# ems.net
KiCad netlist of a schematic drawn in Altium Designer
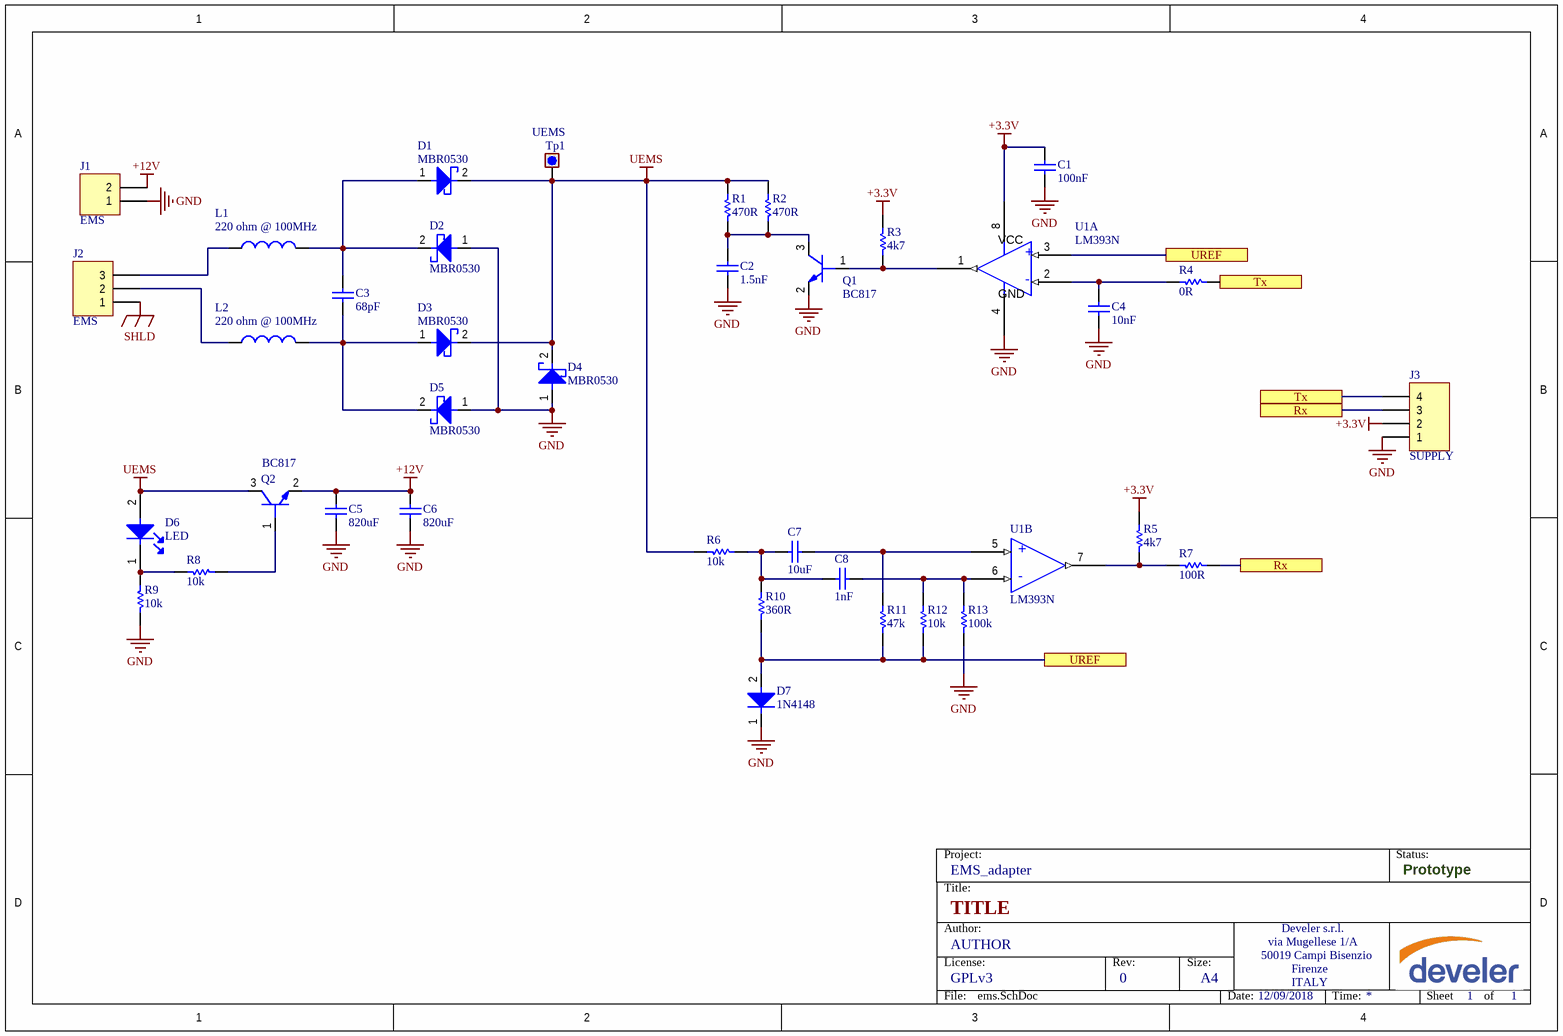
[diagram p0: ems.SchDoc]

(export (version "E")
  (design (tool "Eeschema 10.0.6"))
  (components
    (comp (ref "C1")
      (value "100nF")
      (footprint "0603_[1608]")
      (description "Ceramic X7R 50V")
      (fields (field (name "PUBLISHER") "Altium Limited"))
      (libsource (lib "DEVELER_Library") (part "Cap"))
    )
    (comp (ref "C2")
      (value "1.5nF")
      (footprint "0603_[1608]")
      (description "Ceramic X7R 50V")
      (fields (field (name "PUBLISHER") "Altium Limited"))
      (libsource (lib "DEVELER_Library") (part "Cap"))
    )
    (comp (ref "C3")
      (value "68pF")
      (footprint "0603_[1608]")
      (description "Ceramic X7R 50V")
      (fields (field (name "PUBLISHER") "Altium Limited"))
      (libsource (lib "DEVELER_Library") (part "Cap"))
    )
    (comp (ref "C4")
      (value "10nF")
      (footprint "0603_[1608]")
      (description "Ceramic X7R 50V")
      (fields (field (name "PUBLISHER") "Altium Limited"))
      (libsource (lib "DEVELER_Library") (part "Cap"))
    )
    (comp (ref "C5")
      (value "820uF")
      (footprint "CAP_CYL_3.5mm_D8mm")
      (description "Ceramic X7R 50V")
      (fields (field (name "PUBLISHER") "Altium Limited"))
      (libsource (lib "DEVELER_Library") (part "Cap"))
    )
    (comp (ref "C6")
      (value "820uF")
      (footprint "CAP_CYL_3.5mm_D8mm")
      (description "Ceramic X7R 50V")
      (fields (field (name "PUBLISHER") "Altium Limited"))
      (libsource (lib "DEVELER_Library") (part "Cap"))
    )
    (comp (ref "C7")
      (value "10uF")
      (footprint "0603_[1608]")
      (description "Ceramic X7R 50V")
      (fields (field (name "PUBLISHER") "Altium Limited"))
      (libsource (lib "DEVELER_Library") (part "Cap"))
    )
    (comp (ref "C8")
      (value "1nF")
      (footprint "0603_[1608]")
      (description "Ceramic X7R 50V")
      (fields (field (name "PUBLISHER") "Altium Limited"))
      (libsource (lib "DEVELER_Library") (part "Cap"))
    )
    (comp (ref "D1")
      (value "MBR0530")
      (footprint "SOD-123_K2-A1")
      (description "Schottky Diodes")
      (libsource (lib "develer_library") (part "Diode_SCHOTTKY"))
    )
    (comp (ref "D2")
      (value "MBR0530")
      (footprint "SOD-123_K2-A1")
      (description "Schottky Diodes")
      (libsource (lib "develer_library") (part "Diode_SCHOTTKY"))
    )
    (comp (ref "D3")
      (value "MBR0530")
      (footprint "SOD-123_K2-A1")
      (description "Schottky Diodes")
      (libsource (lib "develer_library") (part "Diode_SCHOTTKY"))
    )
    (comp (ref "D4")
      (value "MBR0530")
      (footprint "SOD-123_K2-A1")
      (description "Schottky Diodes")
      (libsource (lib "develer_library") (part "Diode_SCHOTTKY"))
    )
    (comp (ref "D5")
      (value "MBR0530")
      (footprint "SOD-123_K2-A1")
      (description "Schottky Diodes")
      (libsource (lib "develer_library") (part "Diode_SCHOTTKY"))
    )
    (comp (ref "D6")
      (value "LED")
      (footprint "1206_[3216]_K1-A2_LED")
      (description "Multicolor LED")
      (libsource (lib "develer_library") (part "LED"))
    )
    (comp (ref "D7")
      (value "1N4148")
      (footprint "SOD-80C")
      (libsource (lib "develer_library") (part "Diode"))
    )
    (comp (ref "J1")
      (value "EMS")
      (footprint "CON_2P_WAGO_3.5mm")
      (description "Header, 2-Pin")
      (fields (field (name "PUBLISHER") "Altium Limited"))
      (libsource (lib "Miscellaneous Connectors") (part "Header 2"))
    )
    (comp (ref "J2")
      (value "EMS")
      (footprint "CON_3P_WAGO_3.5mm")
      (description "Header, 3-Pin")
      (fields (field (name "PUBLISHER") "Altium Limited"))
      (libsource (lib "Miscellaneous Connectors") (part "Header 3"))
    )
    (comp (ref "J3")
      (value "SUPPLY")
      (footprint "CON_4P_WAGO_3.5mm")
      (description "Header, 4-Pin")
      (fields (field (name "PUBLISHER") "Altium Limited"))
      (libsource (lib "Miscellaneous Connectors") (part "Header 4"))
    )
    (comp (ref "L1")
      (value "220 ohm @ 100MHz")
      (footprint "0805_[2012]")
      (description "WE 742792022")
      (libsource (lib "DEVELER_Library") (part "Ferrite Bead"))
    )
    (comp (ref "L2")
      (value "220 ohm @ 100MHz")
      (footprint "0805_[2012]")
      (description "WE 742792022")
      (libsource (lib "DEVELER_Library") (part "Ferrite Bead"))
    )
    (comp (ref "Q1")
      (value "BC817")
      (footprint "SOT-23")
      (description "BJT NPN")
      (libsource (lib "develer_library") (part "BC817"))
    )
    (comp (ref "Q2")
      (value "BC817")
      (footprint "SOT-23")
      (description "BJT NPN")
      (libsource (lib "develer_library") (part "BC817"))
    )
    (comp (ref "R1")
      (value "470R")
      (footprint "0603_[1608]")
      (description "Resistor")
      (fields (field (name "PUBLISHER") "Altium Limited"))
      (libsource (lib "DEVELER_Library") (part "Res1"))
    )
    (comp (ref "R2")
      (value "470R")
      (footprint "0603_[1608]")
      (description "Resistor")
      (fields (field (name "PUBLISHER") "Altium Limited"))
      (libsource (lib "DEVELER_Library") (part "Res1"))
    )
    (comp (ref "R3")
      (value "4k7")
      (footprint "0603_[1608]")
      (description "Resistor")
      (fields (field (name "PUBLISHER") "Altium Limited"))
      (libsource (lib "DEVELER_Library") (part "Res1"))
    )
    (comp (ref "R4")
      (value "0R")
      (footprint "0603_[1608]")
      (description "Resistor")
      (fields (field (name "PUBLISHER") "Altium Limited"))
      (libsource (lib "DEVELER_Library") (part "Res1"))
    )
    (comp (ref "R5")
      (value "4k7")
      (footprint "0603_[1608]")
      (description "Resistor")
      (fields (field (name "PUBLISHER") "Altium Limited"))
      (libsource (lib "DEVELER_Library") (part "Res1"))
    )
    (comp (ref "R6")
      (value "10k")
      (footprint "0603_[1608]")
      (description "Resistor")
      (fields (field (name "PUBLISHER") "Altium Limited"))
      (libsource (lib "DEVELER_Library") (part "Res1"))
    )
    (comp (ref "R7")
      (value "100R")
      (footprint "0603_[1608]")
      (description "Resistor")
      (fields (field (name "PUBLISHER") "Altium Limited"))
      (libsource (lib "DEVELER_Library") (part "Res1"))
    )
    (comp (ref "R8")
      (value "10k")
      (footprint "0603_[1608]")
      (description "Resistor")
      (fields (field (name "PUBLISHER") "Altium Limited"))
      (libsource (lib "DEVELER_Library") (part "Res1"))
    )
    (comp (ref "R9")
      (value "10k")
      (footprint "0603_[1608]")
      (description "Resistor")
      (fields (field (name "PUBLISHER") "Altium Limited"))
      (libsource (lib "DEVELER_Library") (part "Res1"))
    )
    (comp (ref "R10")
      (value "360R")
      (footprint "0603_[1608]")
      (description "Resistor")
      (fields (field (name "PUBLISHER") "Altium Limited"))
      (libsource (lib "DEVELER_Library") (part "Res1"))
    )
    (comp (ref "R11")
      (value "47k")
      (footprint "0603_[1608]")
      (description "Resistor")
      (fields (field (name "PUBLISHER") "Altium Limited"))
      (libsource (lib "DEVELER_Library") (part "Res1"))
    )
    (comp (ref "R12")
      (value "10k")
      (footprint "0603_[1608]")
      (description "Resistor")
      (fields (field (name "PUBLISHER") "Altium Limited"))
      (libsource (lib "DEVELER_Library") (part "Res1"))
    )
    (comp (ref "R13")
      (value "100k")
      (footprint "0603_[1608]")
      (description "Resistor")
      (fields (field (name "PUBLISHER") "Altium Limited"))
      (libsource (lib "DEVELER_Library") (part "Res1"))
    )
    (comp (ref "Tp1")
      (value "UEMS")
      (footprint "TEST_POINT_THD_D1.8MM")
      (description "Test point")
      (libsource (lib "DEVELER_Library") (part "Test_point"))
    )
    (comp (ref "U1")
      (value "LM393N")
      (footprint "SOIC8")
      (description "Op Amp.")
      (libsource (lib "develer_library") (part "LM358"))
    )
  )
  (nets
    (net (code "1") (name "+3.3V") (class "Default")
      (node (ref "C1") (pin "2") (pinfunction "2_2") (pintype "passive"))
      (node (ref "J3") (pin "2") (pinfunction "2_2") (pintype "passive"))
      (node (ref "R3") (pin "1") (pinfunction "1_1") (pintype "passive"))
      (node (ref "R5") (pin "1") (pinfunction "1_1") (pintype "passive"))
      (node (ref "U1") (pin "8") (pinfunction "VCC_8") (pintype "power_in"))
    )
    (net (code "2") (name "+12V") (class "Default")
      (node (ref "C5") (pin "2") (pinfunction "2_2") (pintype "passive"))
      (node (ref "C6") (pin "2") (pinfunction "2_2") (pintype "passive"))
      (node (ref "J1") (pin "2") (pinfunction "2_2") (pintype "passive"))
      (node (ref "Q2") (pin "2") (pinfunction "E_2") (pintype "passive"))
    )
    (net (code "3") (name "/Rx") (class "Default")
      (node (ref "J3") (pin "3") (pinfunction "3_3") (pintype "passive"))
      (node (ref "R7") (pin "2") (pinfunction "2_2") (pintype "passive"))
    )
    (net (code "4") (name "/Tx") (class "Default")
      (node (ref "J3") (pin "4") (pinfunction "4_4") (pintype "passive"))
      (node (ref "R4") (pin "2") (pinfunction "2_2") (pintype "passive"))
    )
    (net (code "5") (name "/UREF") (class "Default")
      (node (ref "D7") (pin "2") (pinfunction "A_2") (pintype "passive"))
      (node (ref "R10") (pin "1") (pinfunction "1_1") (pintype "passive"))
      (node (ref "R11") (pin "1") (pinfunction "1_1") (pintype "passive"))
      (node (ref "R12") (pin "1") (pinfunction "1_1") (pintype "passive"))
      (node (ref "U1") (pin "3") (pinfunction "IN+_3") (pintype "input"))
    )
    (net (code "6") (name "GND") (class "Default")
      (node (ref "C1") (pin "1") (pinfunction "1_1") (pintype "passive"))
      (node (ref "C2") (pin "1") (pinfunction "1_1") (pintype "passive"))
      (node (ref "C4") (pin "1") (pinfunction "1_1") (pintype "passive"))
      (node (ref "C5") (pin "1") (pinfunction "1_1") (pintype "passive"))
      (node (ref "C6") (pin "1") (pinfunction "1_1") (pintype "passive"))
      (node (ref "D2") (pin "1") (pinfunction "A_1") (pintype "passive"))
      (node (ref "D4") (pin "1") (pinfunction "A_1") (pintype "passive"))
      (node (ref "D5") (pin "1") (pinfunction "A_1") (pintype "passive"))
      (node (ref "D7") (pin "1") (pinfunction "K_1") (pintype "passive"))
      (node (ref "J1") (pin "1") (pinfunction "1_1") (pintype "passive"))
      (node (ref "J3") (pin "1") (pinfunction "1_1") (pintype "passive"))
      (node (ref "Q1") (pin "2") (pinfunction "E_2") (pintype "passive"))
      (node (ref "R13") (pin "1") (pinfunction "1_1") (pintype "passive"))
      (node (ref "R9") (pin "1") (pinfunction "1_1") (pintype "passive"))
      (node (ref "U1") (pin "4") (pinfunction "GND_4") (pintype "power_in"))
    )
    (net (code "7") (name "Net-(C7-Pad2)") (class "Default")
      (node (ref "C7") (pin "2") (pinfunction "2_2") (pintype "passive"))
      (node (ref "C8") (pin "2") (pinfunction "2_2") (pintype "passive"))
      (node (ref "R10") (pin "2") (pinfunction "2_2") (pintype "passive"))
      (node (ref "R6") (pin "2") (pinfunction "2_2") (pintype "passive"))
    )
    (net (code "8") (name "Net-(D1-A)") (class "Default")
      (node (ref "C3") (pin "2") (pinfunction "2_2") (pintype "passive"))
      (node (ref "D1") (pin "1") (pinfunction "A_1") (pintype "passive"))
      (node (ref "D2") (pin "2") (pinfunction "K_2") (pintype "passive"))
      (node (ref "L1") (pin "1") (pinfunction "1_1") (pintype "passive"))
    )
    (net (code "9") (name "Net-(D3-A)") (class "Default")
      (node (ref "C3") (pin "1") (pinfunction "1_1") (pintype "passive"))
      (node (ref "D3") (pin "1") (pinfunction "A_1") (pintype "passive"))
      (node (ref "D5") (pin "2") (pinfunction "K_2") (pintype "passive"))
      (node (ref "L2") (pin "1") (pinfunction "1_1") (pintype "passive"))
    )
    (net (code "10") (name "Net-(D6-K)") (class "Default")
      (node (ref "D6") (pin "1") (pinfunction "K_1") (pintype "passive"))
      (node (ref "R8") (pin "2") (pinfunction "2_2") (pintype "passive"))
      (node (ref "R9") (pin "2") (pinfunction "2_2") (pintype "passive"))
    )
    (net (code "11") (name "Net-(J2-Pad2)") (class "Default")
      (node (ref "J2") (pin "2") (pinfunction "2_2") (pintype "passive"))
      (node (ref "L2") (pin "2") (pinfunction "2_2") (pintype "passive"))
    )
    (net (code "12") (name "Net-(J2-Pad3)") (class "Default")
      (node (ref "J2") (pin "3") (pinfunction "3_3") (pintype "passive"))
      (node (ref "L1") (pin "2") (pinfunction "2_2") (pintype "passive"))
    )
    (net (code "13") (name "Net-(Q1-B)") (class "Default")
      (node (ref "Q1") (pin "1") (pinfunction "B_1") (pintype "passive"))
      (node (ref "R3") (pin "2") (pinfunction "2_2") (pintype "passive"))
      (node (ref "U1") (pin "1") (pinfunction "OUT_1") (pintype "output"))
    )
    (net (code "14") (name "Net-(Q1-C)") (class "Default")
      (node (ref "C2") (pin "2") (pinfunction "2_2") (pintype "passive"))
      (node (ref "Q1") (pin "3") (pinfunction "C_3") (pintype "passive"))
      (node (ref "R1") (pin "2") (pinfunction "2_2") (pintype "passive"))
      (node (ref "R2") (pin "2") (pinfunction "2_2") (pintype "passive"))
    )
    (net (code "15") (name "Net-(Q2-B)") (class "Default")
      (node (ref "Q2") (pin "1") (pinfunction "B_1") (pintype "passive"))
      (node (ref "R8") (pin "1") (pinfunction "1_1") (pintype "passive"))
    )
    (net (code "16") (name "Net-(U1A-IN-)") (class "Default")
      (node (ref "C4") (pin "2") (pinfunction "2_2") (pintype "passive"))
      (node (ref "R4") (pin "1") (pinfunction "1_1") (pintype "passive"))
      (node (ref "U1") (pin "2") (pinfunction "IN-_2") (pintype "input"))
    )
    (net (code "17") (name "Net-(U1B-IN+)") (class "Default")
      (node (ref "C7") (pin "1") (pinfunction "1_1") (pintype "passive"))
      (node (ref "R11") (pin "2") (pinfunction "2_2") (pintype "passive"))
      (node (ref "U1") (pin "5") (pinfunction "IN+_5") (pintype "input"))
    )
    (net (code "18") (name "Net-(U1B-IN-)") (class "Default")
      (node (ref "C8") (pin "1") (pinfunction "1_1") (pintype "passive"))
      (node (ref "R12") (pin "2") (pinfunction "2_2") (pintype "passive"))
      (node (ref "R13") (pin "2") (pinfunction "2_2") (pintype "passive"))
      (node (ref "U1") (pin "6") (pinfunction "IN-_6") (pintype "input"))
    )
    (net (code "19") (name "Net-(U1B-OUT)") (class "Default")
      (node (ref "R5") (pin "2") (pinfunction "2_2") (pintype "passive"))
      (node (ref "R7") (pin "1") (pinfunction "1_1") (pintype "passive"))
      (node (ref "U1") (pin "7") (pinfunction "OUT_7") (pintype "output"))
    )
    (net (code "20") (name "SHLD") (class "Default")
      (node (ref "J2") (pin "1") (pinfunction "1_1") (pintype "passive"))
    )
    (net (code "21") (name "UEMS") (class "Default")
      (node (ref "D1") (pin "2") (pinfunction "K_2") (pintype "passive"))
      (node (ref "D3") (pin "2") (pinfunction "K_2") (pintype "passive"))
      (node (ref "D4") (pin "2") (pinfunction "K_2") (pintype "passive"))
      (node (ref "D6") (pin "2") (pinfunction "A_2") (pintype "passive"))
      (node (ref "Q2") (pin "3") (pinfunction "C_3") (pintype "passive"))
      (node (ref "R1") (pin "1") (pinfunction "1_1") (pintype "passive"))
      (node (ref "R2") (pin "1") (pinfunction "1_1") (pintype "passive"))
      (node (ref "R6") (pin "1") (pinfunction "1_1") (pintype "passive"))
      (node (ref "Tp1") (pin "1") (pinfunction "1_1") (pintype "passive"))
    )
  )
)
